# Qwiic_Keyboard_Explorer.net
KiCad netlist of a schematic drawn in EAGLE
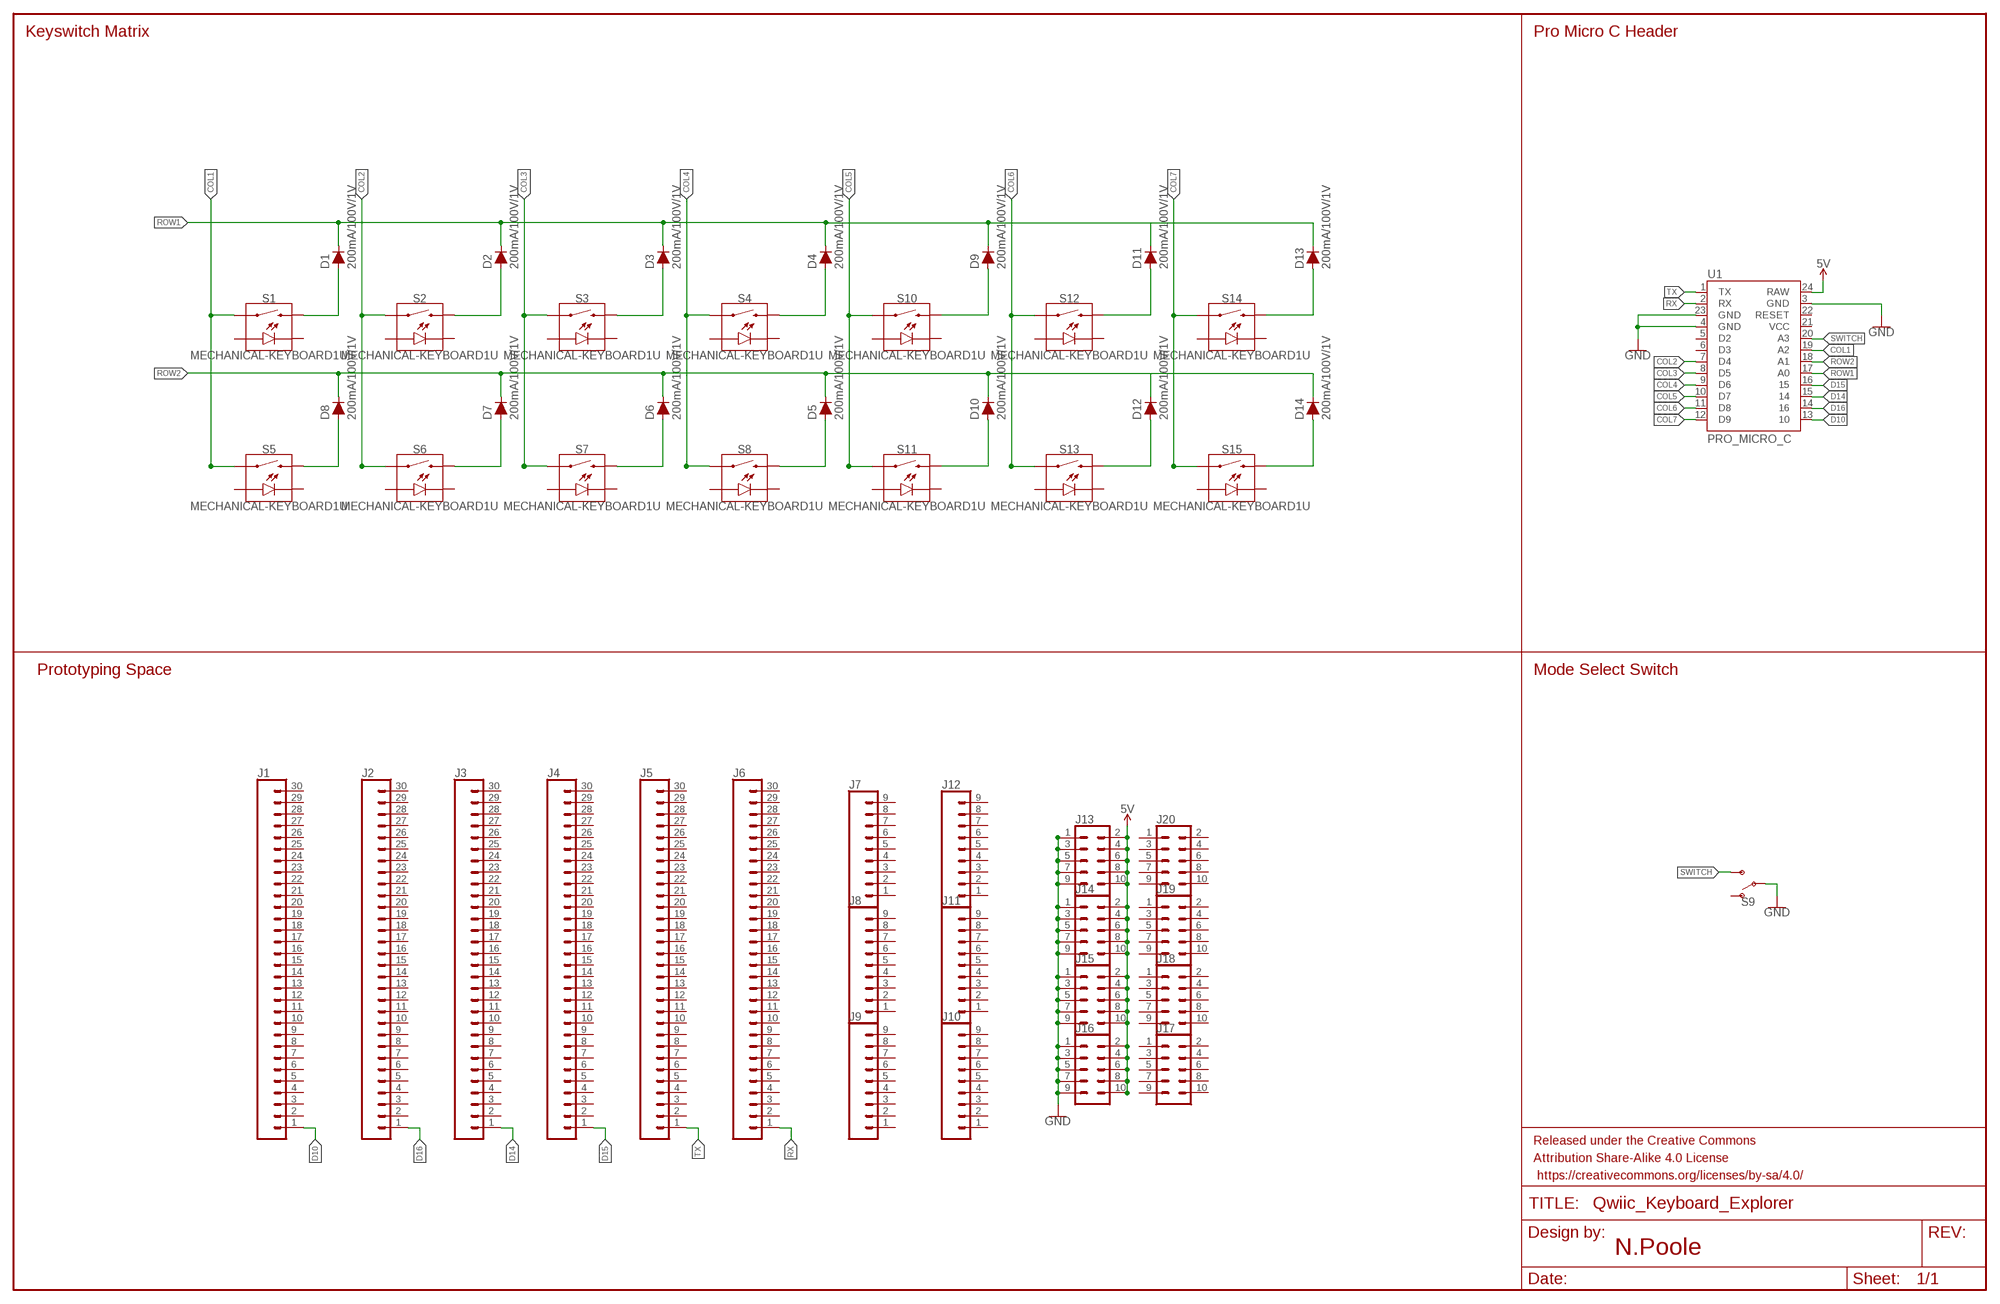
[diagram p0: schematic, sheet 1]

(export (version "E")
  (design (tool "Eeschema 10.0.6"))
  (components
    (comp (ref "D1")
      (value "200mA/100V/1V")
      (footprint "eagle-import:DIODE-1N4148-KIT")
      (libsource (lib "eagle-import") (part "DIODE-KIT"))
    )
    (comp (ref "D2")
      (value "200mA/100V/1V")
      (footprint "eagle-import:DIODE-1N4148-KIT")
      (libsource (lib "eagle-import") (part "DIODE-KIT"))
    )
    (comp (ref "D3")
      (value "200mA/100V/1V")
      (footprint "eagle-import:DIODE-1N4148-KIT")
      (libsource (lib "eagle-import") (part "DIODE-KIT"))
    )
    (comp (ref "D4")
      (value "200mA/100V/1V")
      (footprint "eagle-import:DIODE-1N4148-KIT")
      (libsource (lib "eagle-import") (part "DIODE-KIT"))
    )
    (comp (ref "D5")
      (value "200mA/100V/1V")
      (footprint "eagle-import:DIODE-1N4148-KIT")
      (libsource (lib "eagle-import") (part "DIODE-KIT"))
    )
    (comp (ref "D6")
      (value "200mA/100V/1V")
      (footprint "eagle-import:DIODE-1N4148-KIT")
      (libsource (lib "eagle-import") (part "DIODE-KIT"))
    )
    (comp (ref "D7")
      (value "200mA/100V/1V")
      (footprint "eagle-import:DIODE-1N4148-KIT")
      (libsource (lib "eagle-import") (part "DIODE-KIT"))
    )
    (comp (ref "D8")
      (value "200mA/100V/1V")
      (footprint "eagle-import:DIODE-1N4148-KIT")
      (libsource (lib "eagle-import") (part "DIODE-KIT"))
    )
    (comp (ref "D9")
      (value "200mA/100V/1V")
      (footprint "eagle-import:DIODE-1N4148-KIT")
      (libsource (lib "eagle-import") (part "DIODE-KIT"))
    )
    (comp (ref "D10")
      (value "200mA/100V/1V")
      (footprint "eagle-import:DIODE-1N4148-KIT")
      (libsource (lib "eagle-import") (part "DIODE-KIT"))
    )
    (comp (ref "D11")
      (value "200mA/100V/1V")
      (footprint "eagle-import:DIODE-1N4148-KIT")
      (libsource (lib "eagle-import") (part "DIODE-KIT"))
    )
    (comp (ref "D12")
      (value "200mA/100V/1V")
      (footprint "eagle-import:DIODE-1N4148-KIT")
      (libsource (lib "eagle-import") (part "DIODE-KIT"))
    )
    (comp (ref "D13")
      (value "200mA/100V/1V")
      (footprint "eagle-import:DIODE-1N4148-KIT")
      (libsource (lib "eagle-import") (part "DIODE-KIT"))
    )
    (comp (ref "D14")
      (value "200mA/100V/1V")
      (footprint "eagle-import:DIODE-1N4148-KIT")
      (libsource (lib "eagle-import") (part "DIODE-KIT"))
    )
    (comp (ref "FRAME1")
      (value "FRAME-LEDGER")
      (footprint "eagle-import:CREATIVE_COMMONS")
      (libsource (lib "eagle-import") (part "FRAME-LEDGER"))
    )
    (comp (ref "J1")
      (value "CONN_30NO_SILK")
      (footprint "eagle-import:1X30_NO_SILK")
      (libsource (lib "eagle-import") (part "CONN_30NO_SILK"))
    )
    (comp (ref "J2")
      (value "CONN_30NO_SILK")
      (footprint "eagle-import:1X30_NO_SILK")
      (libsource (lib "eagle-import") (part "CONN_30NO_SILK"))
    )
    (comp (ref "J3")
      (value "CONN_30NO_SILK")
      (footprint "eagle-import:1X30_NO_SILK")
      (libsource (lib "eagle-import") (part "CONN_30NO_SILK"))
    )
    (comp (ref "J4")
      (value "CONN_30NO_SILK")
      (footprint "eagle-import:1X30_NO_SILK")
      (libsource (lib "eagle-import") (part "CONN_30NO_SILK"))
    )
    (comp (ref "J5")
      (value "CONN_30NO_SILK")
      (footprint "eagle-import:1X30_NO_SILK")
      (libsource (lib "eagle-import") (part "CONN_30NO_SILK"))
    )
    (comp (ref "J6")
      (value "CONN_30NO_SILK")
      (footprint "eagle-import:1X30_NO_SILK")
      (libsource (lib "eagle-import") (part "CONN_30NO_SILK"))
    )
    (comp (ref "J7")
      (value "CONN_09NO_SILK")
      (footprint "eagle-import:1X09_NO_SILK")
      (libsource (lib "eagle-import") (part "CONN_09NO_SILK"))
    )
    (comp (ref "J8")
      (value "CONN_09NO_SILK")
      (footprint "eagle-import:1X09_NO_SILK")
      (libsource (lib "eagle-import") (part "CONN_09NO_SILK"))
    )
    (comp (ref "J9")
      (value "CONN_09NO_SILK")
      (footprint "eagle-import:1X09_NO_SILK")
      (libsource (lib "eagle-import") (part "CONN_09NO_SILK"))
    )
    (comp (ref "J10")
      (value "CONN_09NO_SILK")
      (footprint "eagle-import:1X09_NO_SILK")
      (libsource (lib "eagle-import") (part "CONN_09NO_SILK"))
    )
    (comp (ref "J11")
      (value "CONN_09NO_SILK")
      (footprint "eagle-import:1X09_NO_SILK")
      (libsource (lib "eagle-import") (part "CONN_09NO_SILK"))
    )
    (comp (ref "J12")
      (value "CONN_09NO_SILK")
      (footprint "eagle-import:1X09_NO_SILK")
      (libsource (lib "eagle-import") (part "CONN_09NO_SILK"))
    )
    (comp (ref "J13")
      (value "CONN_05X2NO_SILK")
      (footprint "eagle-import:2X5_NOSILK")
      (libsource (lib "eagle-import") (part "CONN_05X2NO_SILK"))
    )
    (comp (ref "J14")
      (value "CONN_05X2NO_SILK")
      (footprint "eagle-import:2X5_NOSILK")
      (libsource (lib "eagle-import") (part "CONN_05X2NO_SILK"))
    )
    (comp (ref "J15")
      (value "CONN_05X2NO_SILK")
      (footprint "eagle-import:2X5_NOSILK")
      (libsource (lib "eagle-import") (part "CONN_05X2NO_SILK"))
    )
    (comp (ref "J16")
      (value "CONN_05X2NO_SILK")
      (footprint "eagle-import:2X5_NOSILK")
      (libsource (lib "eagle-import") (part "CONN_05X2NO_SILK"))
    )
    (comp (ref "J17")
      (value "CONN_05X2NO_SILK")
      (footprint "eagle-import:2X5_NOSILK")
      (libsource (lib "eagle-import") (part "CONN_05X2NO_SILK"))
    )
    (comp (ref "J18")
      (value "CONN_05X2NO_SILK")
      (footprint "eagle-import:2X5_NOSILK")
      (libsource (lib "eagle-import") (part "CONN_05X2NO_SILK"))
    )
    (comp (ref "J19")
      (value "CONN_05X2NO_SILK")
      (footprint "eagle-import:2X5_NOSILK")
      (libsource (lib "eagle-import") (part "CONN_05X2NO_SILK"))
    )
    (comp (ref "J20")
      (value "CONN_05X2NO_SILK")
      (footprint "eagle-import:2X5_NOSILK")
      (libsource (lib "eagle-import") (part "CONN_05X2NO_SILK"))
    )
    (comp (ref "S1")
      (value "MECHANICAL-KEYBOARD1U")
      (footprint "eagle-import:CHERRY-MX-LED-1U")
      (libsource (lib "eagle-import") (part "MECHANICAL-KEYBOARD1U"))
    )
    (comp (ref "S2")
      (value "MECHANICAL-KEYBOARD1U")
      (footprint "eagle-import:CHERRY-MX-LED-1U")
      (libsource (lib "eagle-import") (part "MECHANICAL-KEYBOARD1U"))
    )
    (comp (ref "S3")
      (value "MECHANICAL-KEYBOARD1U")
      (footprint "eagle-import:CHERRY-MX-LED-1U")
      (libsource (lib "eagle-import") (part "MECHANICAL-KEYBOARD1U"))
    )
    (comp (ref "S4")
      (value "MECHANICAL-KEYBOARD1U")
      (footprint "eagle-import:CHERRY-MX-LED-1U")
      (libsource (lib "eagle-import") (part "MECHANICAL-KEYBOARD1U"))
    )
    (comp (ref "S5")
      (value "MECHANICAL-KEYBOARD1U")
      (footprint "eagle-import:CHERRY-MX-LED-1U")
      (libsource (lib "eagle-import") (part "MECHANICAL-KEYBOARD1U"))
    )
    (comp (ref "S6")
      (value "MECHANICAL-KEYBOARD1U")
      (footprint "eagle-import:CHERRY-MX-LED-1U")
      (libsource (lib "eagle-import") (part "MECHANICAL-KEYBOARD1U"))
    )
    (comp (ref "S7")
      (value "MECHANICAL-KEYBOARD1U")
      (footprint "eagle-import:CHERRY-MX-LED-1U")
      (libsource (lib "eagle-import") (part "MECHANICAL-KEYBOARD1U"))
    )
    (comp (ref "S8")
      (value "MECHANICAL-KEYBOARD1U")
      (footprint "eagle-import:CHERRY-MX-LED-1U")
      (libsource (lib "eagle-import") (part "MECHANICAL-KEYBOARD1U"))
    )
    (comp (ref "S9")
      (value "SWITCH-SPDT-PTH-11.6X4.0MM-KIT")
      (footprint "eagle-import:SWITCH_SPDT_PTH_11.6X4.0MM_KIT")
      (libsource (lib "eagle-import") (part "SWITCH-SPDT-PTH-11.6X4.0MM-KIT"))
    )
    (comp (ref "S10")
      (value "MECHANICAL-KEYBOARD1U")
      (footprint "eagle-import:CHERRY-MX-LED-1U")
      (libsource (lib "eagle-import") (part "MECHANICAL-KEYBOARD1U"))
    )
    (comp (ref "S11")
      (value "MECHANICAL-KEYBOARD1U")
      (footprint "eagle-import:CHERRY-MX-LED-1U")
      (libsource (lib "eagle-import") (part "MECHANICAL-KEYBOARD1U"))
    )
    (comp (ref "S12")
      (value "MECHANICAL-KEYBOARD1U")
      (footprint "eagle-import:CHERRY-MX-LED-1U")
      (libsource (lib "eagle-import") (part "MECHANICAL-KEYBOARD1U"))
    )
    (comp (ref "S13")
      (value "MECHANICAL-KEYBOARD1U")
      (footprint "eagle-import:CHERRY-MX-LED-1U")
      (libsource (lib "eagle-import") (part "MECHANICAL-KEYBOARD1U"))
    )
    (comp (ref "S14")
      (value "MECHANICAL-KEYBOARD1U")
      (footprint "eagle-import:CHERRY-MX-LED-1U")
      (libsource (lib "eagle-import") (part "MECHANICAL-KEYBOARD1U"))
    )
    (comp (ref "S15")
      (value "MECHANICAL-KEYBOARD1U")
      (footprint "eagle-import:CHERRY-MX-LED-1U")
      (libsource (lib "eagle-import") (part "MECHANICAL-KEYBOARD1U"))
    )
    (comp (ref "U1")
      (value "PRO_MICRO_C")
      (footprint "eagle-import:PRO_MICRO_C")
      (libsource (lib "eagle-import") (part "PRO_MICRO_C"))
    )
  )
  (nets
    (net (code "1") (name "5V") (class "Default")
      (node (ref "J13") (pin "10") (pinfunction "10_10") (pintype "passive"))
      (node (ref "J13") (pin "2") (pinfunction "2_2") (pintype "passive"))
      (node (ref "J13") (pin "4") (pinfunction "4_4") (pintype "passive"))
      (node (ref "J13") (pin "6") (pinfunction "6_6") (pintype "passive"))
      (node (ref "J13") (pin "8") (pinfunction "8_8") (pintype "passive"))
      (node (ref "J14") (pin "10") (pinfunction "10_10") (pintype "passive"))
      (node (ref "J14") (pin "2") (pinfunction "2_2") (pintype "passive"))
      (node (ref "J14") (pin "4") (pinfunction "4_4") (pintype "passive"))
      (node (ref "J14") (pin "6") (pinfunction "6_6") (pintype "passive"))
      (node (ref "J14") (pin "8") (pinfunction "8_8") (pintype "passive"))
      (node (ref "J15") (pin "10") (pinfunction "10_10") (pintype "passive"))
      (node (ref "J15") (pin "2") (pinfunction "2_2") (pintype "passive"))
      (node (ref "J15") (pin "4") (pinfunction "4_4") (pintype "passive"))
      (node (ref "J15") (pin "6") (pinfunction "6_6") (pintype "passive"))
      (node (ref "J15") (pin "8") (pinfunction "8_8") (pintype "passive"))
      (node (ref "J16") (pin "10") (pinfunction "10_10") (pintype "passive"))
      (node (ref "J16") (pin "2") (pinfunction "2_2") (pintype "passive"))
      (node (ref "J16") (pin "4") (pinfunction "4_4") (pintype "passive"))
      (node (ref "J16") (pin "6") (pinfunction "6_6") (pintype "passive"))
      (node (ref "J16") (pin "8") (pinfunction "8_8") (pintype "passive"))
      (node (ref "U1") (pin "24") (pinfunction "RAW_24") (pintype "bidirectional"))
    )
    (net (code "2") (name "COL1") (class "Default")
      (node (ref "S1") (pin "S1") (pinfunction "1_S1") (pintype "passive"))
      (node (ref "S5") (pin "S1") (pinfunction "1_S1") (pintype "passive"))
      (node (ref "U1") (pin "19") (pinfunction "A2_19") (pintype "bidirectional"))
    )
    (net (code "3") (name "COL2") (class "Default")
      (node (ref "S2") (pin "S1") (pinfunction "1_S1") (pintype "passive"))
      (node (ref "S6") (pin "S1") (pinfunction "1_S1") (pintype "passive"))
      (node (ref "U1") (pin "7") (pinfunction "D4_7") (pintype "bidirectional"))
    )
    (net (code "4") (name "COL3") (class "Default")
      (node (ref "S3") (pin "S1") (pinfunction "1_S1") (pintype "passive"))
      (node (ref "S7") (pin "S1") (pinfunction "1_S1") (pintype "passive"))
      (node (ref "U1") (pin "8") (pinfunction "D5_8") (pintype "bidirectional"))
    )
    (net (code "5") (name "COL4") (class "Default")
      (node (ref "S4") (pin "S1") (pinfunction "1_S1") (pintype "passive"))
      (node (ref "S8") (pin "S1") (pinfunction "1_S1") (pintype "passive"))
      (node (ref "U1") (pin "9") (pinfunction "D6_9") (pintype "bidirectional"))
    )
    (net (code "6") (name "COL5") (class "Default")
      (node (ref "S10") (pin "S1") (pinfunction "1_S1") (pintype "passive"))
      (node (ref "S11") (pin "S1") (pinfunction "1_S1") (pintype "passive"))
      (node (ref "U1") (pin "10") (pinfunction "D7_10") (pintype "bidirectional"))
    )
    (net (code "7") (name "COL6") (class "Default")
      (node (ref "S12") (pin "S1") (pinfunction "1_S1") (pintype "passive"))
      (node (ref "S13") (pin "S1") (pinfunction "1_S1") (pintype "passive"))
      (node (ref "U1") (pin "11") (pinfunction "D8_11") (pintype "bidirectional"))
    )
    (net (code "8") (name "COL7") (class "Default")
      (node (ref "S14") (pin "S1") (pinfunction "1_S1") (pintype "passive"))
      (node (ref "S15") (pin "S1") (pinfunction "1_S1") (pintype "passive"))
      (node (ref "U1") (pin "12") (pinfunction "D9_12") (pintype "bidirectional"))
    )
    (net (code "9") (name "D10") (class "Default")
      (node (ref "J1") (pin "1") (pinfunction "1_1") (pintype "passive"))
      (node (ref "U1") (pin "13") (pinfunction "10_13") (pintype "bidirectional"))
    )
    (net (code "10") (name "D14") (class "Default")
      (node (ref "J3") (pin "1") (pinfunction "1_1") (pintype "passive"))
      (node (ref "U1") (pin "15") (pinfunction "14_15") (pintype "bidirectional"))
    )
    (net (code "11") (name "D15") (class "Default")
      (node (ref "J4") (pin "1") (pinfunction "1_1") (pintype "passive"))
      (node (ref "U1") (pin "16") (pinfunction "15_16") (pintype "bidirectional"))
    )
    (net (code "12") (name "D16") (class "Default")
      (node (ref "J2") (pin "1") (pinfunction "1_1") (pintype "passive"))
      (node (ref "U1") (pin "14") (pinfunction "16_14") (pintype "bidirectional"))
    )
    (net (code "13") (name "GND") (class "Default")
      (node (ref "J13") (pin "1") (pinfunction "1_1") (pintype "passive"))
      (node (ref "J13") (pin "3") (pinfunction "3_3") (pintype "passive"))
      (node (ref "J13") (pin "5") (pinfunction "5_5") (pintype "passive"))
      (node (ref "J13") (pin "7") (pinfunction "7_7") (pintype "passive"))
      (node (ref "J13") (pin "9") (pinfunction "9_9") (pintype "passive"))
      (node (ref "J14") (pin "1") (pinfunction "1_1") (pintype "passive"))
      (node (ref "J14") (pin "3") (pinfunction "3_3") (pintype "passive"))
      (node (ref "J14") (pin "5") (pinfunction "5_5") (pintype "passive"))
      (node (ref "J14") (pin "7") (pinfunction "7_7") (pintype "passive"))
      (node (ref "J14") (pin "9") (pinfunction "9_9") (pintype "passive"))
      (node (ref "J15") (pin "1") (pinfunction "1_1") (pintype "passive"))
      (node (ref "J15") (pin "3") (pinfunction "3_3") (pintype "passive"))
      (node (ref "J15") (pin "5") (pinfunction "5_5") (pintype "passive"))
      (node (ref "J15") (pin "7") (pinfunction "7_7") (pintype "passive"))
      (node (ref "J15") (pin "9") (pinfunction "9_9") (pintype "passive"))
      (node (ref "J16") (pin "1") (pinfunction "1_1") (pintype "passive"))
      (node (ref "J16") (pin "3") (pinfunction "3_3") (pintype "passive"))
      (node (ref "J16") (pin "5") (pinfunction "5_5") (pintype "passive"))
      (node (ref "J16") (pin "7") (pinfunction "7_7") (pintype "passive"))
      (node (ref "J16") (pin "9") (pinfunction "9_9") (pintype "passive"))
      (node (ref "S9") (pin "2") (pinfunction "P_2") (pintype "passive"))
      (node (ref "U1") (pin "23") (pinfunction "GND_23") (pintype "bidirectional"))
      (node (ref "U1") (pin "3") (pinfunction "GND_3") (pintype "bidirectional"))
      (node (ref "U1") (pin "4") (pinfunction "GND_4") (pintype "bidirectional"))
    )
    (net (code "14") (name "Net-(S1-2)") (class "Default")
      (node (ref "D1") (pin "A") (pinfunction "A_A") (pintype "passive"))
      (node (ref "S1") (pin "S2") (pinfunction "2_S2") (pintype "passive"))
    )
    (net (code "15") (name "Net-(S2-2)") (class "Default")
      (node (ref "D2") (pin "A") (pinfunction "A_A") (pintype "passive"))
      (node (ref "S2") (pin "S2") (pinfunction "2_S2") (pintype "passive"))
    )
    (net (code "16") (name "Net-(S3-2)") (class "Default")
      (node (ref "D3") (pin "A") (pinfunction "A_A") (pintype "passive"))
      (node (ref "S3") (pin "S2") (pinfunction "2_S2") (pintype "passive"))
    )
    (net (code "17") (name "Net-(S4-2)") (class "Default")
      (node (ref "D4") (pin "A") (pinfunction "A_A") (pintype "passive"))
      (node (ref "S4") (pin "S2") (pinfunction "2_S2") (pintype "passive"))
    )
    (net (code "18") (name "Net-(S5-2)") (class "Default")
      (node (ref "D8") (pin "A") (pinfunction "A_A") (pintype "passive"))
      (node (ref "S5") (pin "S2") (pinfunction "2_S2") (pintype "passive"))
    )
    (net (code "19") (name "Net-(S6-2)") (class "Default")
      (node (ref "D7") (pin "A") (pinfunction "A_A") (pintype "passive"))
      (node (ref "S6") (pin "S2") (pinfunction "2_S2") (pintype "passive"))
    )
    (net (code "20") (name "Net-(S7-2)") (class "Default")
      (node (ref "D6") (pin "A") (pinfunction "A_A") (pintype "passive"))
      (node (ref "S7") (pin "S2") (pinfunction "2_S2") (pintype "passive"))
    )
    (net (code "21") (name "Net-(S8-2)") (class "Default")
      (node (ref "D5") (pin "A") (pinfunction "A_A") (pintype "passive"))
      (node (ref "S8") (pin "S2") (pinfunction "2_S2") (pintype "passive"))
    )
    (net (code "22") (name "Net-(S10-2)") (class "Default")
      (node (ref "D9") (pin "A") (pinfunction "A_A") (pintype "passive"))
      (node (ref "S10") (pin "S2") (pinfunction "2_S2") (pintype "passive"))
    )
    (net (code "23") (name "Net-(S11-2)") (class "Default")
      (node (ref "D10") (pin "A") (pinfunction "A_A") (pintype "passive"))
      (node (ref "S11") (pin "S2") (pinfunction "2_S2") (pintype "passive"))
    )
    (net (code "24") (name "Net-(S12-2)") (class "Default")
      (node (ref "D11") (pin "A") (pinfunction "A_A") (pintype "passive"))
      (node (ref "S12") (pin "S2") (pinfunction "2_S2") (pintype "passive"))
    )
    (net (code "25") (name "Net-(S13-2)") (class "Default")
      (node (ref "D12") (pin "A") (pinfunction "A_A") (pintype "passive"))
      (node (ref "S13") (pin "S2") (pinfunction "2_S2") (pintype "passive"))
    )
    (net (code "26") (name "Net-(S14-2)") (class "Default")
      (node (ref "D13") (pin "A") (pinfunction "A_A") (pintype "passive"))
      (node (ref "S14") (pin "S2") (pinfunction "2_S2") (pintype "passive"))
    )
    (net (code "27") (name "Net-(S15-2)") (class "Default")
      (node (ref "D14") (pin "A") (pinfunction "A_A") (pintype "passive"))
      (node (ref "S15") (pin "S2") (pinfunction "2_S2") (pintype "passive"))
    )
    (net (code "28") (name "ROW1") (class "Default")
      (node (ref "D1") (pin "C") (pinfunction "C_C") (pintype "passive"))
      (node (ref "D11") (pin "C") (pinfunction "C_C") (pintype "passive"))
      (node (ref "D13") (pin "C") (pinfunction "C_C") (pintype "passive"))
      (node (ref "D2") (pin "C") (pinfunction "C_C") (pintype "passive"))
      (node (ref "D3") (pin "C") (pinfunction "C_C") (pintype "passive"))
      (node (ref "D4") (pin "C") (pinfunction "C_C") (pintype "passive"))
      (node (ref "D9") (pin "C") (pinfunction "C_C") (pintype "passive"))
      (node (ref "U1") (pin "17") (pinfunction "A0_17") (pintype "bidirectional"))
    )
    (net (code "29") (name "ROW2") (class "Default")
      (node (ref "D10") (pin "C") (pinfunction "C_C") (pintype "passive"))
      (node (ref "D12") (pin "C") (pinfunction "C_C") (pintype "passive"))
      (node (ref "D14") (pin "C") (pinfunction "C_C") (pintype "passive"))
      (node (ref "D5") (pin "C") (pinfunction "C_C") (pintype "passive"))
      (node (ref "D6") (pin "C") (pinfunction "C_C") (pintype "passive"))
      (node (ref "D7") (pin "C") (pinfunction "C_C") (pintype "passive"))
      (node (ref "D8") (pin "C") (pinfunction "C_C") (pintype "passive"))
      (node (ref "U1") (pin "18") (pinfunction "A1_18") (pintype "bidirectional"))
    )
    (net (code "30") (name "RX") (class "Default")
      (node (ref "J6") (pin "1") (pinfunction "1_1") (pintype "passive"))
      (node (ref "U1") (pin "2") (pinfunction "RX_2") (pintype "bidirectional"))
    )
    (net (code "31") (name "SWITCH") (class "Default")
      (node (ref "S9") (pin "3") (pinfunction "S_3") (pintype "passive"))
      (node (ref "U1") (pin "20") (pinfunction "A3_20") (pintype "bidirectional"))
    )
    (net (code "32") (name "TX") (class "Default")
      (node (ref "J5") (pin "1") (pinfunction "1_1") (pintype "passive"))
      (node (ref "U1") (pin "1") (pinfunction "TX_1") (pintype "bidirectional"))
    )
    (net (code "33") (name "unconnected-(J1-Pad2)") (class "Default")
      (node (ref "J1") (pin "2") (pinfunction "2_2") (pintype "passive"))
    )
    (net (code "34") (name "unconnected-(J1-Pad3)") (class "Default")
      (node (ref "J1") (pin "3") (pinfunction "3_3") (pintype "passive"))
    )
    (net (code "35") (name "unconnected-(J1-Pad4)") (class "Default")
      (node (ref "J1") (pin "4") (pinfunction "4_4") (pintype "passive"))
    )
    (net (code "36") (name "unconnected-(J1-Pad5)") (class "Default")
      (node (ref "J1") (pin "5") (pinfunction "5_5") (pintype "passive"))
    )
    (net (code "37") (name "unconnected-(J1-Pad6)") (class "Default")
      (node (ref "J1") (pin "6") (pinfunction "6_6") (pintype "passive"))
    )
    (net (code "38") (name "unconnected-(J1-Pad7)") (class "Default")
      (node (ref "J1") (pin "7") (pinfunction "7_7") (pintype "passive"))
    )
    (net (code "39") (name "unconnected-(J1-Pad8)") (class "Default")
      (node (ref "J1") (pin "8") (pinfunction "8_8") (pintype "passive"))
    )
    (net (code "40") (name "unconnected-(J1-Pad9)") (class "Default")
      (node (ref "J1") (pin "9") (pinfunction "9_9") (pintype "passive"))
    )
    (net (code "41") (name "unconnected-(J1-Pad10)") (class "Default")
      (node (ref "J1") (pin "10") (pinfunction "10_10") (pintype "passive"))
    )
    (net (code "42") (name "unconnected-(J1-Pad11)") (class "Default")
      (node (ref "J1") (pin "11") (pinfunction "11_11") (pintype "passive"))
    )
    (net (code "43") (name "unconnected-(J1-Pad12)") (class "Default")
      (node (ref "J1") (pin "12") (pinfunction "12_12") (pintype "passive"))
    )
    (net (code "44") (name "unconnected-(J1-Pad13)") (class "Default")
      (node (ref "J1") (pin "13") (pinfunction "13_13") (pintype "passive"))
    )
    (net (code "45") (name "unconnected-(J1-Pad14)") (class "Default")
      (node (ref "J1") (pin "14") (pinfunction "14_14") (pintype "passive"))
    )
    (net (code "46") (name "unconnected-(J1-Pad15)") (class "Default")
      (node (ref "J1") (pin "15") (pinfunction "15_15") (pintype "passive"))
    )
    (net (code "47") (name "unconnected-(J1-Pad16)") (class "Default")
      (node (ref "J1") (pin "16") (pinfunction "16_16") (pintype "passive"))
    )
    (net (code "48") (name "unconnected-(J1-Pad17)") (class "Default")
      (node (ref "J1") (pin "17") (pinfunction "17_17") (pintype "passive"))
    )
    (net (code "49") (name "unconnected-(J1-Pad18)") (class "Default")
      (node (ref "J1") (pin "18") (pinfunction "18_18") (pintype "passive"))
    )
    (net (code "50") (name "unconnected-(J1-Pad19)") (class "Default")
      (node (ref "J1") (pin "19") (pinfunction "19_19") (pintype "passive"))
    )
    (net (code "51") (name "unconnected-(J1-Pad20)") (class "Default")
      (node (ref "J1") (pin "20") (pinfunction "20_20") (pintype "passive"))
    )
    (net (code "52") (name "unconnected-(J1-Pad21)") (class "Default")
      (node (ref "J1") (pin "21") (pinfunction "21_21") (pintype "passive"))
    )
    (net (code "53") (name "unconnected-(J1-Pad22)") (class "Default")
      (node (ref "J1") (pin "22") (pinfunction "22_22") (pintype "passive"))
    )
    (net (code "54") (name "unconnected-(J1-Pad23)") (class "Default")
      (node (ref "J1") (pin "23") (pinfunction "23_23") (pintype "passive"))
    )
    (net (code "55") (name "unconnected-(J1-Pad24)") (class "Default")
      (node (ref "J1") (pin "24") (pinfunction "24_24") (pintype "passive"))
    )
    (net (code "56") (name "unconnected-(J1-Pad25)") (class "Default")
      (node (ref "J1") (pin "25") (pinfunction "25_25") (pintype "passive"))
    )
    (net (code "57") (name "unconnected-(J1-Pad26)") (class "Default")
      (node (ref "J1") (pin "26") (pinfunction "26_26") (pintype "passive"))
    )
    (net (code "58") (name "unconnected-(J1-Pad27)") (class "Default")
      (node (ref "J1") (pin "27") (pinfunction "27_27") (pintype "passive"))
    )
    (net (code "59") (name "unconnected-(J1-Pad28)") (class "Default")
      (node (ref "J1") (pin "28") (pinfunction "28_28") (pintype "passive"))
    )
    (net (code "60") (name "unconnected-(J1-Pad29)") (class "Default")
      (node (ref "J1") (pin "29") (pinfunction "29_29") (pintype "passive"))
    )
    (net (code "61") (name "unconnected-(J1-Pad30)") (class "Default")
      (node (ref "J1") (pin "30") (pinfunction "30_30") (pintype "passive"))
    )
    (net (code "62") (name "unconnected-(J2-Pad2)") (class "Default")
      (node (ref "J2") (pin "2") (pinfunction "2_2") (pintype "passive"))
    )
    (net (code "63") (name "unconnected-(J2-Pad3)") (class "Default")
      (node (ref "J2") (pin "3") (pinfunction "3_3") (pintype "passive"))
    )
    (net (code "64") (name "unconnected-(J2-Pad4)") (class "Default")
      (node (ref "J2") (pin "4") (pinfunction "4_4") (pintype "passive"))
    )
    (net (code "65") (name "unconnected-(J2-Pad5)") (class "Default")
      (node (ref "J2") (pin "5") (pinfunction "5_5") (pintype "passive"))
    )
    (net (code "66") (name "unconnected-(J2-Pad6)") (class "Default")
      (node (ref "J2") (pin "6") (pinfunction "6_6") (pintype "passive"))
    )
    (net (code "67") (name "unconnected-(J2-Pad7)") (class "Default")
      (node (ref "J2") (pin "7") (pinfunction "7_7") (pintype "passive"))
    )
    (net (code "68") (name "unconnected-(J2-Pad8)") (class "Default")
      (node (ref "J2") (pin "8") (pinfunction "8_8") (pintype "passive"))
    )
    (net (code "69") (name "unconnected-(J2-Pad9)") (class "Default")
      (node (ref "J2") (pin "9") (pinfunction "9_9") (pintype "passive"))
    )
    (net (code "70") (name "unconnected-(J2-Pad10)") (class "Default")
      (node (ref "J2") (pin "10") (pinfunction "10_10") (pintype "passive"))
    )
    (net (code "71") (name "unconnected-(J2-Pad11)") (class "Default")
      (node (ref "J2") (pin "11") (pinfunction "11_11") (pintype "passive"))
    )
    (net (code "72") (name "unconnected-(J2-Pad12)") (class "Default")
      (node (ref "J2") (pin "12") (pinfunction "12_12") (pintype "passive"))
    )
    (net (code "73") (name "unconnected-(J2-Pad13)") (class "Default")
      (node (ref "J2") (pin "13") (pinfunction "13_13") (pintype "passive"))
    )
    (net (code "74") (name "unconnected-(J2-Pad14)") (class "Default")
      (node (ref "J2") (pin "14") (pinfunction "14_14") (pintype "passive"))
    )
    (net (code "75") (name "unconnected-(J2-Pad15)") (class "Default")
      (node (ref "J2") (pin "15") (pinfunction "15_15") (pintype "passive"))
    )
    (net (code "76") (name "unconnected-(J2-Pad16)") (class "Default")
      (node (ref "J2") (pin "16") (pinfunction "16_16") (pintype "passive"))
    )
    (net (code "77") (name "unconnected-(J2-Pad17)") (class "Default")
      (node (ref "J2") (pin "17") (pinfunction "17_17") (pintype "passive"))
    )
    (net (code "78") (name "unconnected-(J2-Pad18)") (class "Default")
      (node (ref "J2") (pin "18") (pinfunction "18_18") (pintype "passive"))
    )
    (net (code "79") (name "unconnected-(J2-Pad19)") (class "Default")
      (node (ref "J2") (pin "19") (pinfunction "19_19") (pintype "passive"))
    )
    (net (code "80") (name "unconnected-(J2-Pad20)") (class "Default")
      (node (ref "J2") (pin "20") (pinfunction "20_20") (pintype "passive"))
    )
    (net (code "81") (name "unconnected-(J2-Pad21)") (class "Default")
      (node (ref "J2") (pin "21") (pinfunction "21_21") (pintype "passive"))
    )
    (net (code "82") (name "unconnected-(J2-Pad22)") (class "Default")
      (node (ref "J2") (pin "22") (pinfunction "22_22") (pintype "passive"))
    )
    (net (code "83") (name "unconnected-(J2-Pad23)") (class "Default")
      (node (ref "J2") (pin "23") (pinfunction "23_23") (pintype "passive"))
    )
    (net (code "84") (name "unconnected-(J2-Pad24)") (class "Default")
      (node (ref "J2") (pin "24") (pinfunction "24_24") (pintype "passive"))
    )
    (net (code "85") (name "unconnected-(J2-Pad25)") (class "Default")
      (node (ref "J2") (pin "25") (pinfunction "25_25") (pintype "passive"))
    )
    (net (code "86") (name "unconnected-(J2-Pad26)") (class "Default")
      (node (ref "J2") (pin "26") (pinfunction "26_26") (pintype "passive"))
    )
    (net (code "87") (name "unconnected-(J2-Pad27)") (class "Default")
      (node (ref "J2") (pin "27") (pinfunction "27_27") (pintype "passive"))
    )
    (net (code "88") (name "unconnected-(J2-Pad28)") (class "Default")
      (node (ref "J2") (pin "28") (pinfunction "28_28") (pintype "passive"))
    )
    (net (code "89") (name "unconnected-(J2-Pad29)") (class "Default")
      (node (ref "J2") (pin "29") (pinfunction "29_29") (pintype "passive"))
    )
    (net (code "90") (name "unconnected-(J2-Pad30)") (class "Default")
      (node (ref "J2") (pin "30") (pinfunction "30_30") (pintype "passive"))
    )
    (net (code "91") (name "unconnected-(J3-Pad2)") (class "Default")
      (node (ref "J3") (pin "2") (pinfunction "2_2") (pintype "passive"))
    )
    (net (code "92") (name "unconnected-(J3-Pad3)") (class "Default")
      (node (ref "J3") (pin "3") (pinfunction "3_3") (pintype "passive"))
    )
    (net (code "93") (name "unconnected-(J3-Pad4)") (class "Default")
      (node (ref "J3") (pin "4") (pinfunction "4_4") (pintype "passive"))
    )
    (net (code "94") (name "unconnected-(J3-Pad5)") (class "Default")
      (node (ref "J3") (pin "5") (pinfunction "5_5") (pintype "passive"))
    )
    (net (code "95") (name "unconnected-(J3-Pad6)") (class "Default")
      (node (ref "J3") (pin "6") (pinfunction "6_6") (pintype "passive"))
    )
    (net (code "96") (name "unconnected-(J3-Pad7)") (class "Default")
      (node (ref "J3") (pin "7") (pinfunction "7_7") (pintype "passive"))
    )
    (net (code "97") (name "unconnected-(J3-Pad8)") (class "Default")
      (node (ref "J3") (pin "8") (pinfunction "8_8") (pintype "passive"))
    )
    (net (code "98") (name "unconnected-(J3-Pad9)") (class "Default")
      (node (ref "J3") (pin "9") (pinfunction "9_9") (pintype "passive"))
    )
    (net (code "99") (name "unconnected-(J3-Pad10)") (class "Default")
      (node (ref "J3") (pin "10") (pinfunction "10_10") (pintype "passive"))
    )
    (net (code "100") (name "unconnected-(J3-Pad11)") (class "Default")
      (node (ref "J3") (pin "11") (pinfunction "11_11") (pintype "passive"))
    )
    (net (code "101") (name "unconnected-(J3-Pad12)") (class "Default")
      (node (ref "J3") (pin "12") (pinfunction "12_12") (pintype "passive"))
    )
    (net (code "102") (name "unconnected-(J3-Pad13)") (class "Default")
      (node (ref "J3") (pin "13") (pinfunction "13_13") (pintype "passive"))
    )
    (net (code "103") (name "unconnected-(J3-Pad14)") (class "Default")
      (node (ref "J3") (pin "14") (pinfunction "14_14") (pintype "passive"))
    )
    (net (code "104") (name "unconnected-(J3-Pad15)") (class "Default")
      (node (ref "J3") (pin "15") (pinfunction "15_15") (pintype "passive"))
    )
    (net (code "105") (name "unconnected-(J3-Pad16)") (class "Default")
      (node (ref "J3") (pin "16") (pinfunction "16_16") (pintype "passive"))
    )
    (net (code "106") (name "unconnected-(J3-Pad17)") (class "Default")
      (node (ref "J3") (pin "17") (pinfunction "17_17") (pintype "passive"))
    )
    (net (code "107") (name "unconnected-(J3-Pad18)") (class "Default")
      (node (ref "J3") (pin "18") (pinfunction "18_18") (pintype "passive"))
    )
    (net (code "108") (name "unconnected-(J3-Pad19)") (class "Default")
      (node (ref "J3") (pin "19") (pinfunction "19_19") (pintype "passive"))
    )
    (net (code "109") (name "unconnected-(J3-Pad20)") (class "Default")
      (node (ref "J3") (pin "20") (pinfunction "20_20") (pintype "passive"))
    )
    (net (code "110") (name "unconnected-(J3-Pad21)") (class "Default")
      (node (ref "J3") (pin "21") (pinfunction "21_21") (pintype "passive"))
    )
    (net (code "111") (name "unconnected-(J3-Pad22)") (class "Default")
      (node (ref "J3") (pin "22") (pinfunction "22_22") (pintype "passive"))
    )
    (net (code "112") (name "unconnected-(J3-Pad23)") (class "Default")
      (node (ref "J3") (pin "23") (pinfunction "23_23") (pintype "passive"))
    )
    (net (code "113") (name "unconnected-(J3-Pad24)") (class "Default")
      (node (ref "J3") (pin "24") (pinfunction "24_24") (pintype "passive"))
    )
    (net (code "114") (name "unconnected-(J3-Pad25)") (class "Default")
      (node (ref "J3") (pin "25") (pinfunction "25_25") (pintype "passive"))
    )
    (net (code "115") (name "unconnected-(J3-Pad26)") (class "Default")
      (node (ref "J3") (pin "26") (pinfunction "26_26") (pintype "passive"))
    )
    (net (code "116") (name "unconnected-(J3-Pad27)") (class "Default")
      (node (ref "J3") (pin "27") (pinfunction "27_27") (pintype "passive"))
    )
    (net (code "117") (name "unconnected-(J3-Pad28)") (class "Default")
      (node (ref "J3") (pin "28") (pinfunction "28_28") (pintype "passive"))
    )
    (net (code "118") (name "unconnected-(J3-Pad29)") (class "Default")
      (node (ref "J3") (pin "29") (pinfunction "29_29") (pintype "passive"))
    )
    (net (code "119") (name "unconnected-(J3-Pad30)") (class "Default")
      (node (ref "J3") (pin "30") (pinfunction "30_30") (pintype "passive"))
    )
    (net (code "120") (name "unconnected-(J4-Pad2)") (class "Default")
      (node (ref "J4") (pin "2") (pinfunction "2_2") (pintype "passive"))
    )
    (net (code "121") (name "unconnected-(J4-Pad3)") (class "Default")
      (node (ref "J4") (pin "3") (pinfunction "3_3") (pintype "passive"))
    )
    (net (code "122") (name "unconnected-(J4-Pad4)") (class "Default")
      (node (ref "J4") (pin "4") (pinfunction "4_4") (pintype "passive"))
    )
    (net (code "123") (name "unconnected-(J4-Pad5)") (class "Default")
      (node (ref "J4") (pin "5") (pinfunction "5_5") (pintype "passive"))
    )
    (net (code "124") (name "unconnected-(J4-Pad6)") (class "Default")
      (node (ref "J4") (pin "6") (pinfunction "6_6") (pintype "passive"))
    )
    (net (code "125") (name "unconnected-(J4-Pad7)") (class "Default")
      (node (ref "J4") (pin "7") (pinfunction "7_7") (pintype "passive"))
    )
    (net (code "126") (name "unconnected-(J4-Pad8)") (class "Default")
      (node (ref "J4") (pin "8") (pinfunction "8_8") (pintype "passive"))
    )
    (net (code "127") (name "unconnected-(J4-Pad9)") (class "Default")
      (node (ref "J4") (pin "9") (pinfunction "9_9") (pintype "passive"))
    )
    (net (code "128") (name "unconnected-(J4-Pad10)") (class "Default")
      (node (ref "J4") (pin "10") (pinfunction "10_10") (pintype "passive"))
    )
    (net (code "129") (name "unconnected-(J4-Pad11)") (class "Default")
      (node (ref "J4") (pin "11") (pinfunction "11_11") (pintype "passive"))
    )
    (net (code "130") (name "unconnected-(J4-Pad12)") (class "Default")
      (node (ref "J4") (pin "12") (pinfunction "12_12") (pintype "passive"))
    )
    (net (code "131") (name "unconnected-(J4-Pad13)") (class "Default")
      (node (ref "J4") (pin "13") (pinfunction "13_13") (pintype "passive"))
    )
    (net (code "132") (name "unconnected-(J4-Pad14)") (class "Default")
      (node (ref "J4") (pin "14") (pinfunction "14_14") (pintype "passive"))
    )
    (net (code "133") (name "unconnected-(J4-Pad15)") (class "Default")
      (node (ref "J4") (pin "15") (pinfunction "15_15") (pintype "passive"))
    )
    (net (code "134") (name "unconnected-(J4-Pad16)") (class "Default")
      (node (ref "J4") (pin "16") (pinfunction "16_16") (pintype "passive"))
    )
    (net (code "135") (name "unconnected-(J4-Pad17)") (class "Default")
      (node (ref "J4") (pin "17") (pinfunction "17_17") (pintype "passive"))
    )
    (net (code "136") (name "unconnected-(J4-Pad18)") (class "Default")
      (node (ref "J4") (pin "18") (pinfunction "18_18") (pintype "passive"))
    )
    (net (code "137") (name "unconnected-(J4-Pad19)") (class "Default")
      (node (ref "J4") (pin "19") (pinfunction "19_19") (pintype "passive"))
    )
    (net (code "138") (name "unconnected-(J4-Pad20)") (class "Default")
      (node (ref "J4") (pin "20") (pinfunction "20_20") (pintype "passive"))
    )
    (net (code "139") (name "unconnected-(J4-Pad21)") (class "Default")
      (node (ref "J4") (pin "21") (pinfunction "21_21") (pintype "passive"))
    )
    (net (code "140") (name "unconnected-(J4-Pad22)") (class "Default")
      (node (ref "J4") (pin "22") (pinfunction "22_22") (pintype "passive"))
    )
    (net (code "141") (name "unconnected-(J4-Pad23)") (class "Default")
      (node (ref "J4") (pin "23") (pinfunction "23_23") (pintype "passive"))
    )
    (net (code "142") (name "unconnected-(J4-Pad24)") (class "Default")
      (node (ref "J4") (pin "24") (pinfunction "24_24") (pintype "passive"))
    )
    (net (code "143") (name "unconnected-(J4-Pad25)") (class "Default")
      (node (ref "J4") (pin "25") (pinfunction "25_25") (pintype "passive"))
    )
    (net (code "144") (name "unconnected-(J4-Pad26)") (class "Default")
      (node (ref "J4") (pin "26") (pinfunction "26_26") (pintype "passive"))
    )
    (net (code "145") (name "unconnected-(J4-Pad27)") (class "Default")
      (node (ref "J4") (pin "27") (pinfunction "27_27") (pintype "passive"))
    )
    (net (code "146") (name "unconnected-(J4-Pad28)") (class "Default")
      (node (ref "J4") (pin "28") (pinfunction "28_28") (pintype "passive"))
    )
    (net (code "147") (name "unconnected-(J4-Pad29)") (class "Default")
      (node (ref "J4") (pin "29") (pinfunction "29_29") (pintype "passive"))
    )
    (net (code "148") (name "unconnected-(J4-Pad30)") (class "Default")
      (node (ref "J4") (pin "30") (pinfunction "30_30") (pintype "passive"))
    )
    (net (code "149") (name "unconnected-(J5-Pad2)") (class "Default")
      (node (ref "J5") (pin "2") (pinfunction "2_2") (pintype "passive"))
    )
    (net (code "150") (name "unconnected-(J5-Pad3)") (class "Default")
      (node (ref "J5") (pin "3") (pinfunction "3_3") (pintype "passive"))
    )
    (net (code "151") (name "unconnected-(J5-Pad4)") (class "Default")
      (node (ref "J5") (pin "4") (pinfunction "4_4") (pintype "passive"))
    )
    (net (code "152") (name "unconnected-(J5-Pad5)") (class "Default")
      (node (ref "J5") (pin "5") (pinfunction "5_5") (pintype "passive"))
    )
    (net (code "153") (name "unconnected-(J5-Pad6)") (class "Default")
      (node (ref "J5") (pin "6") (pinfunction "6_6") (pintype "passive"))
    )
    (net (code "154") (name "unconnected-(J5-Pad7)") (class "Default")
      (node (ref "J5") (pin "7") (pinfunction "7_7") (pintype "passive"))
    )
    (net (code "155") (name "unconnected-(J5-Pad8)") (class "Default")
      (node (ref "J5") (pin "8") (pinfunction "8_8") (pintype "passive"))
    )
    (net (code "156") (name "unconnected-(J5-Pad9)") (class "Default")
      (node (ref "J5") (pin "9") (pinfunction "9_9") (pintype "passive"))
    )
    (net (code "157") (name "unconnected-(J5-Pad10)") (class "Default")
      (node (ref "J5") (pin "10") (pinfunction "10_10") (pintype "passive"))
    )
    (net (code "158") (name "unconnected-(J5-Pad11)") (class "Default")
      (node (ref "J5") (pin "11") (pinfunction "11_11") (pintype "passive"))
    )
    (net (code "159") (name "unconnected-(J5-Pad12)") (class "Default")
      (node (ref "J5") (pin "12") (pinfunction "12_12") (pintype "passive"))
    )
    (net (code "160") (name "unconnected-(J5-Pad13)") (class "Default")
      (node (ref "J5") (pin "13") (pinfunction "13_13") (pintype "passive"))
    )
    (net (code "161") (name "unconnected-(J5-Pad14)") (class "Default")
      (node (ref "J5") (pin "14") (pinfunction "14_14") (pintype "passive"))
    )
    (net (code "162") (name "unconnected-(J5-Pad15)") (class "Default")
      (node (ref "J5") (pin "15") (pinfunction "15_15") (pintype "passive"))
    )
    (net (code "163") (name "unconnected-(J5-Pad16)") (class "Default")
      (node (ref "J5") (pin "16") (pinfunction "16_16") (pintype "passive"))
    )
    (net (code "164") (name "unconnected-(J5-Pad17)") (class "Default")
      (node (ref "J5") (pin "17") (pinfunction "17_17") (pintype "passive"))
    )
    (net (code "165") (name "unconnected-(J5-Pad18)") (class "Default")
      (node (ref "J5") (pin "18") (pinfunction "18_18") (pintype "passive"))
    )
    (net (code "166") (name "unconnected-(J5-Pad19)") (class "Default")
      (node (ref "J5") (pin "19") (pinfunction "19_19") (pintype "passive"))
    )
    (net (code "167") (name "unconnected-(J5-Pad20)") (class "Default")
      (node (ref "J5") (pin "20") (pinfunction "20_20") (pintype "passive"))
    )
    (net (code "168") (name "unconnected-(J5-Pad21)") (class "Default")
      (node (ref "J5") (pin "21") (pinfunction "21_21") (pintype "passive"))
    )
    (net (code "169") (name "unconnected-(J5-Pad22)") (class "Default")
      (node (ref "J5") (pin "22") (pinfunction "22_22") (pintype "passive"))
    )
    (net (code "170") (name "unconnected-(J5-Pad23)") (class "Default")
      (node (ref "J5") (pin "23") (pinfunction "23_23") (pintype "passive"))
    )
    (net (code "171") (name "unconnected-(J5-Pad24)") (class "Default")
      (node (ref "J5") (pin "24") (pinfunction "24_24") (pintype "passive"))
    )
    (net (code "172") (name "unconnected-(J5-Pad25)") (class "Default")
      (node (ref "J5") (pin "25") (pinfunction "25_25") (pintype "passive"))
    )
    (net (code "173") (name "unconnected-(J5-Pad26)") (class "Default")
      (node (ref "J5") (pin "26") (pinfunction "26_26") (pintype "passive"))
    )
    (net (code "174") (name "unconnected-(J5-Pad27)") (class "Default")
      (node (ref "J5") (pin "27") (pinfunction "27_27") (pintype "passive"))
    )
    (net (code "175") (name "unconnected-(J5-Pad28)") (class "Default")
      (node (ref "J5") (pin "28") (pinfunction "28_28") (pintype "passive"))
    )
    (net (code "176") (name "unconnected-(J5-Pad29)") (class "Default")
      (node (ref "J5") (pin "29") (pinfunction "29_29") (pintype "passive"))
    )
    (net (code "177") (name "unconnected-(J5-Pad30)") (class "Default")
      (node (ref "J5") (pin "30") (pinfunction "30_30") (pintype "passive"))
    )
    (net (code "178") (name "unconnected-(J6-Pad2)") (class "Default")
      (node (ref "J6") (pin "2") (pinfunction "2_2") (pintype "passive"))
    )
    (net (code "179") (name "unconnected-(J6-Pad3)") (class "Default")
      (node (ref "J6") (pin "3") (pinfunction "3_3") (pintype "passive"))
    )
    (net (code "180") (name "unconnected-(J6-Pad4)") (class "Default")
      (node (ref "J6") (pin "4") (pinfunction "4_4") (pintype "passive"))
    )
    (net (code "181") (name "unconnected-(J6-Pad5)") (class "Default")
      (node (ref "J6") (pin "5") (pinfunction "5_5") (pintype "passive"))
    )
    (net (code "182") (name "unconnected-(J6-Pad6)") (class "Default")
      (node (ref "J6") (pin "6") (pinfunction "6_6") (pintype "passive"))
    )
    (net (code "183") (name "unconnected-(J6-Pad7)") (class "Default")
      (node (ref "J6") (pin "7") (pinfunction "7_7") (pintype "passive"))
    )
    (net (code "184") (name "unconnected-(J6-Pad8)") (class "Default")
      (node (ref "J6") (pin "8") (pinfunction "8_8") (pintype "passive"))
    )
    (net (code "185") (name "unconnected-(J6-Pad9)") (class "Default")
      (node (ref "J6") (pin "9") (pinfunction "9_9") (pintype "passive"))
    )
    (net (code "186") (name "unconnected-(J6-Pad10)") (class "Default")
      (node (ref "J6") (pin "10") (pinfunction "10_10") (pintype "passive"))
    )
    (net (code "187") (name "unconnected-(J6-Pad11)") (class "Default")
      (node (ref "J6") (pin "11") (pinfunction "11_11") (pintype "passive"))
    )
    (net (code "188") (name "unconnected-(J6-Pad12)") (class "Default")
      (node (ref "J6") (pin "12") (pinfunction "12_12") (pintype "passive"))
    )
    (net (code "189") (name "unconnected-(J6-Pad13)") (class "Default")
      (node (ref "J6") (pin "13") (pinfunction "13_13") (pintype "passive"))
    )
    (net (code "190") (name "unconnected-(J6-Pad14)") (class "Default")
      (node (ref "J6") (pin "14") (pinfunction "14_14") (pintype "passive"))
    )
    (net (code "191") (name "unconnected-(J6-Pad15)") (class "Default")
      (node (ref "J6") (pin "15") (pinfunction "15_15") (pintype "passive"))
    )
    (net (code "192") (name "unconnected-(J6-Pad16)") (class "Default")
      (node (ref "J6") (pin "16") (pinfunction "16_16") (pintype "passive"))
    )
    (net (code "193") (name "unconnected-(J6-Pad17)") (class "Default")
      (node (ref "J6") (pin "17") (pinfunction "17_17") (pintype "passive"))
    )
    (net (code "194") (name "unconnected-(J6-Pad18)") (class "Default")
      (node (ref "J6") (pin "18") (pinfunction "18_18") (pintype "passive"))
    )
    (net (code "195") (name "unconnected-(J6-Pad19)") (class "Default")
      (node (ref "J6") (pin "19") (pinfunction "19_19") (pintype "passive"))
    )
    (net (code "196") (name "unconnected-(J6-Pad20)") (class "Default")
      (node (ref "J6") (pin "20") (pinfunction "20_20") (pintype "passive"))
    )
    (net (code "197") (name "unconnected-(J6-Pad21)") (class "Default")
      (node (ref "J6") (pin "21") (pinfunction "21_21") (pintype "passive"))
    )
    (net (code "198") (name "unconnected-(J6-Pad22)") (class "Default")
      (node (ref "J6") (pin "22") (pinfunction "22_22") (pintype "passive"))
    )
    (net (code "199") (name "unconnected-(J6-Pad23)") (class "Default")
      (node (ref "J6") (pin "23") (pinfunction "23_23") (pintype "passive"))
    )
    (net (code "200") (name "unconnected-(J6-Pad24)") (class "Default")
      (node (ref "J6") (pin "24") (pinfunction "24_24") (pintype "passive"))
    )
    (net (code "201") (name "unconnected-(J6-Pad25)") (class "Default")
      (node (ref "J6") (pin "25") (pinfunction "25_25") (pintype "passive"))
    )
    (net (code "202") (name "unconnected-(J6-Pad26)") (class "Default")
      (node (ref "J6") (pin "26") (pinfunction "26_26") (pintype "passive"))
    )
    (net (code "203") (name "unconnected-(J6-Pad27)") (class "Default")
      (node (ref "J6") (pin "27") (pinfunction "27_27") (pintype "passive"))
    )
    (net (code "204") (name "unconnected-(J6-Pad28)") (class "Default")
      (node (ref "J6") (pin "28") (pinfunction "28_28") (pintype "passive"))
    )
    (net (code "205") (name "unconnected-(J6-Pad29)") (class "Default")
      (node (ref "J6") (pin "29") (pinfunction "29_29") (pintype "passive"))
    )
    (net (code "206") (name "unconnected-(J6-Pad30)") (class "Default")
      (node (ref "J6") (pin "30") (pinfunction "30_30") (pintype "passive"))
    )
    (net (code "207") (name "unconnected-(J7-Pad1)") (class "Default")
      (node (ref "J7") (pin "1") (pinfunction "1_1") (pintype "passive"))
    )
    (net (code "208") (name "unconnected-(J7-Pad2)") (class "Default")
      (node (ref "J7") (pin "2") (pinfunction "2_2") (pintype "passive"))
    )
    (net (code "209") (name "unconnected-(J7-Pad3)") (class "Default")
      (node (ref "J7") (pin "3") (pinfunction "3_3") (pintype "passive"))
    )
    (net (code "210") (name "unconnected-(J7-Pad4)") (class "Default")
      (node (ref "J7") (pin "4") (pinfunction "4_4") (pintype "passive"))
    )
    (net (code "211") (name "unconnected-(J7-Pad5)") (class "Default")
      (node (ref "J7") (pin "5") (pinfunction "5_5") (pintype "passive"))
    )
    (net (code "212") (name "unconnected-(J7-Pad6)") (class "Default")
      (node (ref "J7") (pin "6") (pinfunction "6_6") (pintype "passive"))
    )
    (net (code "213") (name "unconnected-(J7-Pad7)") (class "Default")
      (node (ref "J7") (pin "7") (pinfunction "7_7") (pintype "passive"))
    )
    (net (code "214") (name "unconnected-(J7-Pad8)") (class "Default")
      (node (ref "J7") (pin "8") (pinfunction "8_8") (pintype "passive"))
    )
    (net (code "215") (name "unconnected-(J7-Pad9)") (class "Default")
      (node (ref "J7") (pin "9") (pinfunction "9_9") (pintype "passive"))
    )
    (net (code "216") (name "unconnected-(J8-Pad1)") (class "Default")
      (node (ref "J8") (pin "1") (pinfunction "1_1") (pintype "passive"))
    )
    (net (code "217") (name "unconnected-(J8-Pad2)") (class "Default")
      (node (ref "J8") (pin "2") (pinfunction "2_2") (pintype "passive"))
    )
    (net (code "218") (name "unconnected-(J8-Pad3)") (class "Default")
      (node (ref "J8") (pin "3") (pinfunction "3_3") (pintype "passive"))
    )
    (net (code "219") (name "unconnected-(J8-Pad4)") (class "Default")
      (node (ref "J8") (pin "4") (pinfunction "4_4") (pintype "passive"))
    )
    (net (code "220") (name "unconnected-(J8-Pad5)") (class "Default")
      (node (ref "J8") (pin "5") (pinfunction "5_5") (pintype "passive"))
    )
    (net (code "221") (name "unconnected-(J8-Pad6)") (class "Default")
      (node (ref "J8") (pin "6") (pinfunction "6_6") (pintype "passive"))
    )
    (net (code "222") (name "unconnected-(J8-Pad7)") (class "Default")
      (node (ref "J8") (pin "7") (pinfunction "7_7") (pintype "passive"))
    )
    (net (code "223") (name "unconnected-(J8-Pad8)") (class "Default")
      (node (ref "J8") (pin "8") (pinfunction "8_8") (pintype "passive"))
    )
    (net (code "224") (name "unconnected-(J8-Pad9)") (class "Default")
      (node (ref "J8") (pin "9") (pinfunction "9_9") (pintype "passive"))
    )
    (net (code "225") (name "unconnected-(J9-Pad1)") (class "Default")
      (node (ref "J9") (pin "1") (pinfunction "1_1") (pintype "passive"))
    )
    (net (code "226") (name "unconnected-(J9-Pad2)") (class "Default")
      (node (ref "J9") (pin "2") (pinfunction "2_2") (pintype "passive"))
    )
    (net (code "227") (name "unconnected-(J9-Pad3)") (class "Default")
      (node (ref "J9") (pin "3") (pinfunction "3_3") (pintype "passive"))
    )
    (net (code "228") (name "unconnected-(J9-Pad4)") (class "Default")
      (node (ref "J9") (pin "4") (pinfunction "4_4") (pintype "passive"))
    )
    (net (code "229") (name "unconnected-(J9-Pad5)") (class "Default")
      (node (ref "J9") (pin "5") (pinfunction "5_5") (pintype "passive"))
    )
    (net (code "230") (name "unconnected-(J9-Pad6)") (class "Default")
      (node (ref "J9") (pin "6") (pinfunction "6_6") (pintype "passive"))
    )
    (net (code "231") (name "unconnected-(J9-Pad7)") (class "Default")
      (node (ref "J9") (pin "7") (pinfunction "7_7") (pintype "passive"))
    )
    (net (code "232") (name "unconnected-(J9-Pad8)") (class "Default")
      (node (ref "J9") (pin "8") (pinfunction "8_8") (pintype "passive"))
    )
    (net (code "233") (name "unconnected-(J9-Pad9)") (class "Default")
      (node (ref "J9") (pin "9") (pinfunction "9_9") (pintype "passive"))
    )
    (net (code "234") (name "unconnected-(J10-Pad1)") (class "Default")
      (node (ref "J10") (pin "1") (pinfunction "1_1") (pintype "passive"))
    )
    (net (code "235") (name "unconnected-(J10-Pad2)") (class "Default")
      (node (ref "J10") (pin "2") (pinfunction "2_2") (pintype "passive"))
    )
    (net (code "236") (name "unconnected-(J10-Pad3)") (class "Default")
      (node (ref "J10") (pin "3") (pinfunction "3_3") (pintype "passive"))
    )
    (net (code "237") (name "unconnected-(J10-Pad4)") (class "Default")
      (node (ref "J10") (pin "4") (pinfunction "4_4") (pintype "passive"))
    )
    (net (code "238") (name "unconnected-(J10-Pad5)") (class "Default")
      (node (ref "J10") (pin "5") (pinfunction "5_5") (pintype "passive"))
    )
    (net (code "239") (name "unconnected-(J10-Pad6)") (class "Default")
      (node (ref "J10") (pin "6") (pinfunction "6_6") (pintype "passive"))
    )
    (net (code "240") (name "unconnected-(J10-Pad7)") (class "Default")
      (node (ref "J10") (pin "7") (pinfunction "7_7") (pintype "passive"))
    )
    (net (code "241") (name "unconnected-(J10-Pad8)") (class "Default")
      (node (ref "J10") (pin "8") (pinfunction "8_8") (pintype "passive"))
    )
    (net (code "242") (name "unconnected-(J10-Pad9)") (class "Default")
      (node (ref "J10") (pin "9") (pinfunction "9_9") (pintype "passive"))
    )
    (net (code "243") (name "unconnected-(J11-Pad1)") (class "Default")
      (node (ref "J11") (pin "1") (pinfunction "1_1") (pintype "passive"))
    )
    (net (code "244") (name "unconnected-(J11-Pad2)") (class "Default")
      (node (ref "J11") (pin "2") (pinfunction "2_2") (pintype "passive"))
    )
    (net (code "245") (name "unconnected-(J11-Pad3)") (class "Default")
      (node (ref "J11") (pin "3") (pinfunction "3_3") (pintype "passive"))
    )
    (net (code "246") (name "unconnected-(J11-Pad4)") (class "Default")
      (node (ref "J11") (pin "4") (pinfunction "4_4") (pintype "passive"))
    )
    (net (code "247") (name "unconnected-(J11-Pad5)") (class "Default")
      (node (ref "J11") (pin "5") (pinfunction "5_5") (pintype "passive"))
    )
    (net (code "248") (name "unconnected-(J11-Pad6)") (class "Default")
      (node (ref "J11") (pin "6") (pinfunction "6_6") (pintype "passive"))
    )
    (net (code "249") (name "unconnected-(J11-Pad7)") (class "Default")
      (node (ref "J11") (pin "7") (pinfunction "7_7") (pintype "passive"))
    )
    (net (code "250") (name "unconnected-(J11-Pad8)") (class "Default")
      (node (ref "J11") (pin "8") (pinfunction "8_8") (pintype "passive"))
    )
    (net (code "251") (name "unconnected-(J11-Pad9)") (class "Default")
      (node (ref "J11") (pin "9") (pinfunction "9_9") (pintype "passive"))
    )
    (net (code "252") (name "unconnected-(J12-Pad1)") (class "Default")
      (node (ref "J12") (pin "1") (pinfunction "1_1") (pintype "passive"))
    )
    (net (code "253") (name "unconnected-(J12-Pad2)") (class "Default")
      (node (ref "J12") (pin "2") (pinfunction "2_2") (pintype "passive"))
    )
    (net (code "254") (name "unconnected-(J12-Pad3)") (class "Default")
      (node (ref "J12") (pin "3") (pinfunction "3_3") (pintype "passive"))
    )
    (net (code "255") (name "unconnected-(J12-Pad4)") (class "Default")
      (node (ref "J12") (pin "4") (pinfunction "4_4") (pintype "passive"))
    )
    (net (code "256") (name "unconnected-(J12-Pad5)") (class "Default")
      (node (ref "J12") (pin "5") (pinfunction "5_5") (pintype "passive"))
    )
    (net (code "257") (name "unconnected-(J12-Pad6)") (class "Default")
      (node (ref "J12") (pin "6") (pinfunction "6_6") (pintype "passive"))
    )
    (net (code "258") (name "unconnected-(J12-Pad7)") (class "Default")
      (node (ref "J12") (pin "7") (pinfunction "7_7") (pintype "passive"))
    )
    (net (code "259") (name "unconnected-(J12-Pad8)") (class "Default")
      (node (ref "J12") (pin "8") (pinfunction "8_8") (pintype "passive"))
    )
    (net (code "260") (name "unconnected-(J12-Pad9)") (class "Default")
      (node (ref "J12") (pin "9") (pinfunction "9_9") (pintype "passive"))
    )
    (net (code "261") (name "unconnected-(J17-Pad1)") (class "Default")
      (node (ref "J17") (pin "1") (pinfunction "1_1") (pintype "passive"))
    )
    (net (code "262") (name "unconnected-(J17-Pad2)") (class "Default")
      (node (ref "J17") (pin "2") (pinfunction "2_2") (pintype "passive"))
    )
    (net (code "263") (name "unconnected-(J17-Pad3)") (class "Default")
      (node (ref "J17") (pin "3") (pinfunction "3_3") (pintype "passive"))
    )
    (net (code "264") (name "unconnected-(J17-Pad4)") (class "Default")
      (node (ref "J17") (pin "4") (pinfunction "4_4") (pintype "passive"))
    )
    (net (code "265") (name "unconnected-(J17-Pad5)") (class "Default")
      (node (ref "J17") (pin "5") (pinfunction "5_5") (pintype "passive"))
    )
    (net (code "266") (name "unconnected-(J17-Pad6)") (class "Default")
      (node (ref "J17") (pin "6") (pinfunction "6_6") (pintype "passive"))
    )
    (net (code "267") (name "unconnected-(J17-Pad7)") (class "Default")
      (node (ref "J17") (pin "7") (pinfunction "7_7") (pintype "passive"))
    )
    (net (code "268") (name "unconnected-(J17-Pad8)") (class "Default")
      (node (ref "J17") (pin "8") (pinfunction "8_8") (pintype "passive"))
    )
    (net (code "269") (name "unconnected-(J17-Pad9)") (class "Default")
      (node (ref "J17") (pin "9") (pinfunction "9_9") (pintype "passive"))
    )
    (net (code "270") (name "unconnected-(J17-Pad10)") (class "Default")
      (node (ref "J17") (pin "10") (pinfunction "10_10") (pintype "passive"))
    )
    (net (code "271") (name "unconnected-(J18-Pad1)") (class "Default")
      (node (ref "J18") (pin "1") (pinfunction "1_1") (pintype "passive"))
    )
    (net (code "272") (name "unconnected-(J18-Pad2)") (class "Default")
      (node (ref "J18") (pin "2") (pinfunction "2_2") (pintype "passive"))
    )
    (net (code "273") (name "unconnected-(J18-Pad3)") (class "Default")
      (node (ref "J18") (pin "3") (pinfunction "3_3") (pintype "passive"))
    )
    (net (code "274") (name "unconnected-(J18-Pad4)") (class "Default")
      (node (ref "J18") (pin "4") (pinfunction "4_4") (pintype "passive"))
    )
    (net (code "275") (name "unconnected-(J18-Pad5)") (class "Default")
      (node (ref "J18") (pin "5") (pinfunction "5_5") (pintype "passive"))
    )
    (net (code "276") (name "unconnected-(J18-Pad6)") (class "Default")
      (node (ref "J18") (pin "6") (pinfunction "6_6") (pintype "passive"))
    )
    (net (code "277") (name "unconnected-(J18-Pad7)") (class "Default")
      (node (ref "J18") (pin "7") (pinfunction "7_7") (pintype "passive"))
    )
    (net (code "278") (name "unconnected-(J18-Pad8)") (class "Default")
      (node (ref "J18") (pin "8") (pinfunction "8_8") (pintype "passive"))
    )
    (net (code "279") (name "unconnected-(J18-Pad9)") (class "Default")
      (node (ref "J18") (pin "9") (pinfunction "9_9") (pintype "passive"))
    )
    (net (code "280") (name "unconnected-(J18-Pad10)") (class "Default")
      (node (ref "J18") (pin "10") (pinfunction "10_10") (pintype "passive"))
    )
    (net (code "281") (name "unconnected-(J19-Pad1)") (class "Default")
      (node (ref "J19") (pin "1") (pinfunction "1_1") (pintype "passive"))
    )
    (net (code "282") (name "unconnected-(J19-Pad2)") (class "Default")
      (node (ref "J19") (pin "2") (pinfunction "2_2") (pintype "passive"))
    )
    (net (code "283") (name "unconnected-(J19-Pad3)") (class "Default")
      (node (ref "J19") (pin "3") (pinfunction "3_3") (pintype "passive"))
    )
    (net (code "284") (name "unconnected-(J19-Pad4)") (class "Default")
      (node (ref "J19") (pin "4") (pinfunction "4_4") (pintype "passive"))
    )
    (net (code "285") (name "unconnected-(J19-Pad5)") (class "Default")
      (node (ref "J19") (pin "5") (pinfunction "5_5") (pintype "passive"))
    )
    (net (code "286") (name "unconnected-(J19-Pad6)") (class "Default")
      (node (ref "J19") (pin "6") (pinfunction "6_6") (pintype "passive"))
    )
    (net (code "287") (name "unconnected-(J19-Pad7)") (class "Default")
      (node (ref "J19") (pin "7") (pinfunction "7_7") (pintype "passive"))
    )
    (net (code "288") (name "unconnected-(J19-Pad8)") (class "Default")
      (node (ref "J19") (pin "8") (pinfunction "8_8") (pintype "passive"))
    )
    (net (code "289") (name "unconnected-(J19-Pad9)") (class "Default")
      (node (ref "J19") (pin "9") (pinfunction "9_9") (pintype "passive"))
    )
    (net (code "290") (name "unconnected-(J19-Pad10)") (class "Default")
      (node (ref "J19") (pin "10") (pinfunction "10_10") (pintype "passive"))
    )
    (net (code "291") (name "unconnected-(J20-Pad1)") (class "Default")
      (node (ref "J20") (pin "1") (pinfunction "1_1") (pintype "passive"))
    )
    (net (code "292") (name "unconnected-(J20-Pad2)") (class "Default")
      (node (ref "J20") (pin "2") (pinfunction "2_2") (pintype "passive"))
    )
    (net (code "293") (name "unconnected-(J20-Pad3)") (class "Default")
      (node (ref "J20") (pin "3") (pinfunction "3_3") (pintype "passive"))
    )
    (net (code "294") (name "unconnected-(J20-Pad4)") (class "Default")
      (node (ref "J20") (pin "4") (pinfunction "4_4") (pintype "passive"))
    )
    (net (code "295") (name "unconnected-(J20-Pad5)") (class "Default")
      (node (ref "J20") (pin "5") (pinfunction "5_5") (pintype "passive"))
    )
    (net (code "296") (name "unconnected-(J20-Pad6)") (class "Default")
      (node (ref "J20") (pin "6") (pinfunction "6_6") (pintype "passive"))
    )
    (net (code "297") (name "unconnected-(J20-Pad7)") (class "Default")
      (node (ref "J20") (pin "7") (pinfunction "7_7") (pintype "passive"))
    )
    (net (code "298") (name "unconnected-(J20-Pad8)") (class "Default")
      (node (ref "J20") (pin "8") (pinfunction "8_8") (pintype "passive"))
    )
    (net (code "299") (name "unconnected-(J20-Pad9)") (class "Default")
      (node (ref "J20") (pin "9") (pinfunction "9_9") (pintype "passive"))
    )
    (net (code "300") (name "unconnected-(J20-Pad10)") (class "Default")
      (node (ref "J20") (pin "10") (pinfunction "10_10") (pintype "passive"))
    )
    (net (code "301") (name "unconnected-(S1-C-PadK)") (class "Default")
      (node (ref "S1") (pin "K") (pinfunction "C_K") (pintype "passive"))
    )
    (net (code "302") (name "unconnected-(S1-PadA)") (class "Default")
      (node (ref "S1") (pin "A") (pinfunction "A_A") (pintype "passive"))
    )
    (net (code "303") (name "unconnected-(S2-C-PadK)") (class "Default")
      (node (ref "S2") (pin "K") (pinfunction "C_K") (pintype "passive"))
    )
    (net (code "304") (name "unconnected-(S2-PadA)") (class "Default")
      (node (ref "S2") (pin "A") (pinfunction "A_A") (pintype "passive"))
    )
    (net (code "305") (name "unconnected-(S3-C-PadK)") (class "Default")
      (node (ref "S3") (pin "K") (pinfunction "C_K") (pintype "passive"))
    )
    (net (code "306") (name "unconnected-(S3-PadA)") (class "Default")
      (node (ref "S3") (pin "A") (pinfunction "A_A") (pintype "passive"))
    )
    (net (code "307") (name "unconnected-(S4-C-PadK)") (class "Default")
      (node (ref "S4") (pin "K") (pinfunction "C_K") (pintype "passive"))
    )
    (net (code "308") (name "unconnected-(S4-PadA)") (class "Default")
      (node (ref "S4") (pin "A") (pinfunction "A_A") (pintype "passive"))
    )
    (net (code "309") (name "unconnected-(S5-C-PadK)") (class "Default")
      (node (ref "S5") (pin "K") (pinfunction "C_K") (pintype "passive"))
    )
    (net (code "310") (name "unconnected-(S5-PadA)") (class "Default")
      (node (ref "S5") (pin "A") (pinfunction "A_A") (pintype "passive"))
    )
    (net (code "311") (name "unconnected-(S6-C-PadK)") (class "Default")
      (node (ref "S6") (pin "K") (pinfunction "C_K") (pintype "passive"))
    )
    (net (code "312") (name "unconnected-(S6-PadA)") (class "Default")
      (node (ref "S6") (pin "A") (pinfunction "A_A") (pintype "passive"))
    )
    (net (code "313") (name "unconnected-(S7-C-PadK)") (class "Default")
      (node (ref "S7") (pin "K") (pinfunction "C_K") (pintype "passive"))
    )
    (net (code "314") (name "unconnected-(S7-PadA)") (class "Default")
      (node (ref "S7") (pin "A") (pinfunction "A_A") (pintype "passive"))
    )
    (net (code "315") (name "unconnected-(S8-C-PadK)") (class "Default")
      (node (ref "S8") (pin "K") (pinfunction "C_K") (pintype "passive"))
    )
    (net (code "316") (name "unconnected-(S8-PadA)") (class "Default")
      (node (ref "S8") (pin "A") (pinfunction "A_A") (pintype "passive"))
    )
    (net (code "317") (name "unconnected-(S9-O-Pad1)") (class "Default")
      (node (ref "S9") (pin "1") (pinfunction "O_1") (pintype "passive"))
    )
    (net (code "318") (name "unconnected-(S10-C-PadK)") (class "Default")
      (node (ref "S10") (pin "K") (pinfunction "C_K") (pintype "passive"))
    )
    (net (code "319") (name "unconnected-(S10-PadA)") (class "Default")
      (node (ref "S10") (pin "A") (pinfunction "A_A") (pintype "passive"))
    )
    (net (code "320") (name "unconnected-(S11-C-PadK)") (class "Default")
      (node (ref "S11") (pin "K") (pinfunction "C_K") (pintype "passive"))
    )
    (net (code "321") (name "unconnected-(S11-PadA)") (class "Default")
      (node (ref "S11") (pin "A") (pinfunction "A_A") (pintype "passive"))
    )
    (net (code "322") (name "unconnected-(S12-C-PadK)") (class "Default")
      (node (ref "S12") (pin "K") (pinfunction "C_K") (pintype "passive"))
    )
    (net (code "323") (name "unconnected-(S12-PadA)") (class "Default")
      (node (ref "S12") (pin "A") (pinfunction "A_A") (pintype "passive"))
    )
    (net (code "324") (name "unconnected-(S13-C-PadK)") (class "Default")
      (node (ref "S13") (pin "K") (pinfunction "C_K") (pintype "passive"))
    )
    (net (code "325") (name "unconnected-(S13-PadA)") (class "Default")
      (node (ref "S13") (pin "A") (pinfunction "A_A") (pintype "passive"))
    )
    (net (code "326") (name "unconnected-(S14-C-PadK)") (class "Default")
      (node (ref "S14") (pin "K") (pinfunction "C_K") (pintype "passive"))
    )
    (net (code "327") (name "unconnected-(S14-PadA)") (class "Default")
      (node (ref "S14") (pin "A") (pinfunction "A_A") (pintype "passive"))
    )
    (net (code "328") (name "unconnected-(S15-C-PadK)") (class "Default")
      (node (ref "S15") (pin "K") (pinfunction "C_K") (pintype "passive"))
    )
    (net (code "329") (name "unconnected-(S15-PadA)") (class "Default")
      (node (ref "S15") (pin "A") (pinfunction "A_A") (pintype "passive"))
    )
    (net (code "330") (name "unconnected-(U1-D2-Pad5)") (class "Default")
      (node (ref "U1") (pin "5") (pinfunction "D2_5") (pintype "bidirectional"))
    )
    (net (code "331") (name "unconnected-(U1-D3-Pad6)") (class "Default")
      (node (ref "U1") (pin "6") (pinfunction "D3_6") (pintype "bidirectional"))
    )
    (net (code "332") (name "unconnected-(U1-RESET-Pad22)") (class "Default")
      (node (ref "U1") (pin "22") (pinfunction "RESET_22") (pintype "bidirectional"))
    )
    (net (code "333") (name "unconnected-(U1-VCC-Pad21)") (class "Default")
      (node (ref "U1") (pin "21") (pinfunction "VCC_21") (pintype "bidirectional"))
    )
  )
)
